# Duty_cycle_SSR.net
KiCad netlist of a schematic drawn in Altium Designer
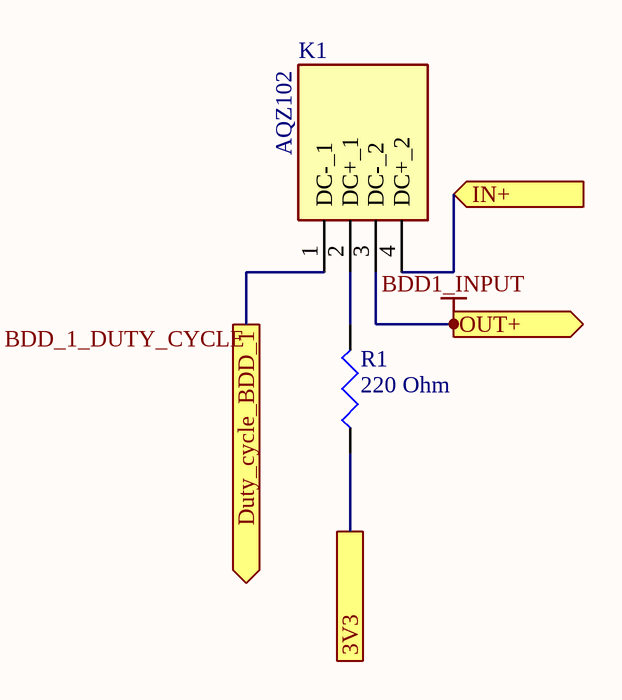
[diagram p0: Duty cycle SSR.SchDoc]

(export (version "E")
  (design (tool "Eeschema 10.0.6"))
  (components
    (comp (ref "K1")
      (value "AQZ102")
      (footprint "AQZ102")
      (description "Relay or Contactor")
      (fields (field (name "MOUSER PART NUMBER") "769-AQZ102"))
      (libsource (lib "*") (part "AQZ102"))
    )
    (comp (ref "R1")
      (value "220 Ohm")
      (footprint "J1-0603")
      (description "Resistor")
      (fields (field (name "PUBLISHER") "Altium Limited"))
      (libsource (lib "Miscellaneous Devices") (part "Res3"))
    )
  )
  (nets
    (net (code "1") (name "/3V3") (class "Default")
      (node (ref "R1") (pin "1") (pinfunction "1_1") (pintype "passive"))
    )
    (net (code "2") (name "/BDD_1_DUTY_CYCLE") (class "Default")
      (node (ref "K1") (pin "1") (pinfunction "DC-_1_1") (pintype "passive"))
    )
    (net (code "3") (name "/IN+") (class "Default")
      (node (ref "K1") (pin "4") (pinfunction "DC+_2_4") (pintype "passive"))
    )
    (net (code "4") (name "BDD1_INPUT") (class "Default")
      (node (ref "K1") (pin "3") (pinfunction "DC-_2_3") (pintype "passive"))
    )
    (net (code "5") (name "Net-(K1-DC+_1)") (class "Default")
      (node (ref "K1") (pin "2") (pinfunction "DC+_1_2") (pintype "passive"))
      (node (ref "R1") (pin "2") (pinfunction "2_2") (pintype "passive"))
    )
  )
)
